# Sheet1.net
KiCad netlist of a schematic drawn in Altium Designer
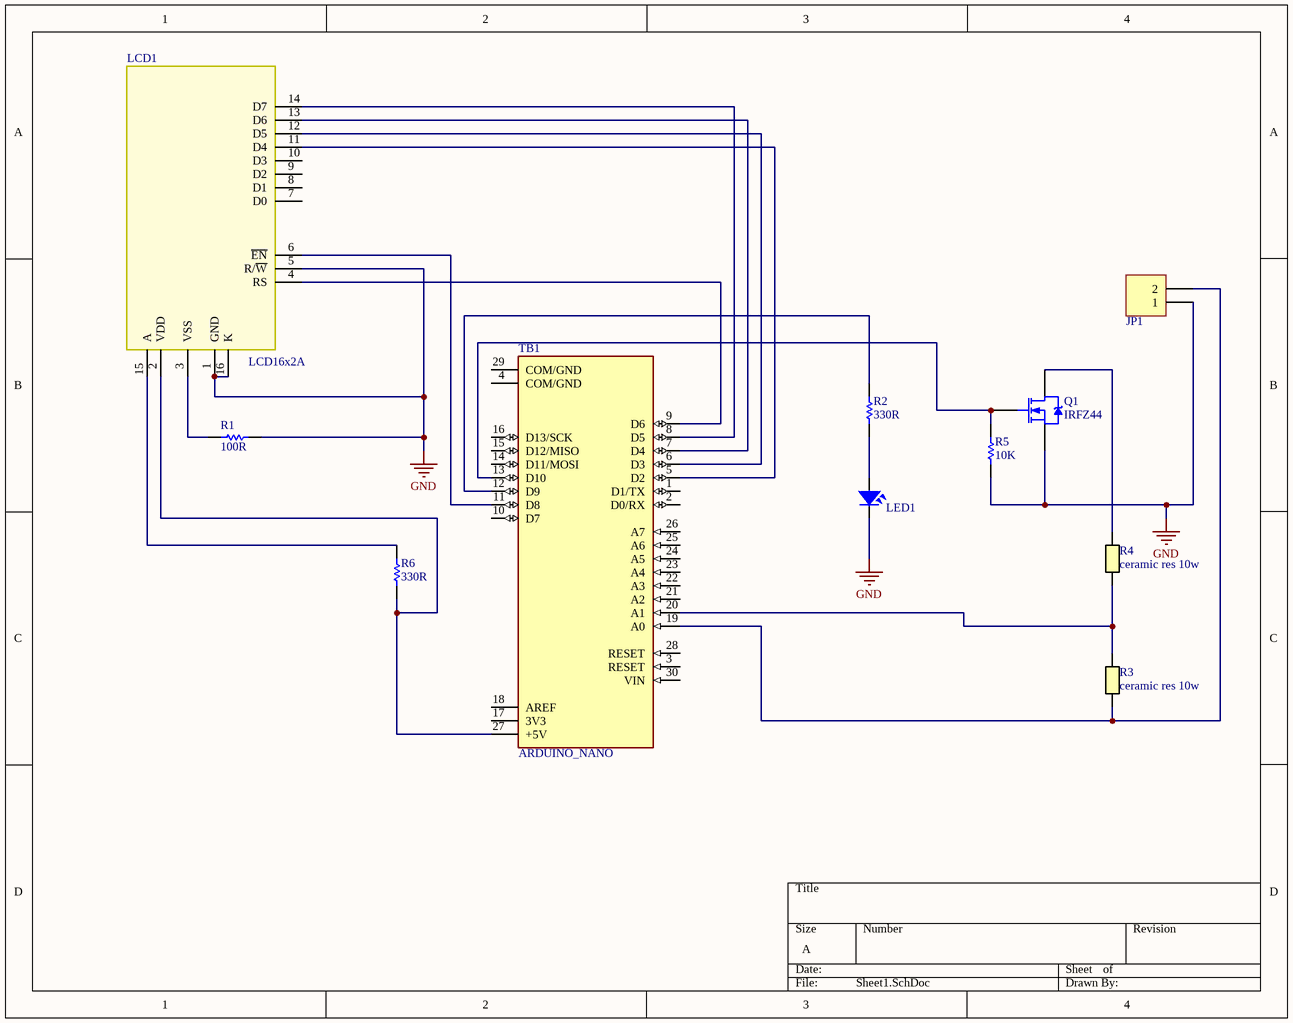
[diagram p0: Sheet1.SchDoc]

(export (version "E")
  (design (tool "Eeschema 10.0.6"))
  (components
    (comp (ref "JP1")
      (value "Header 2_1")
      (footprint "HED2")
      (description "Header, 2-Pin")
      (fields (field (name "MANUFACTURER") "Generic Components"))
      (libsource (lib "syhaunguyen") (part "Header 2_1"))
    )
    (comp (ref "LCD1")
      (value "LCD16x2A")
      (footprint "LCD16X2")
      (description "LCD dipslay 16 char, 2 line")
      (libsource (lib "syhaunguyen") (part "LCD16x2"))
    )
    (comp (ref "LED1")
      (value "LED")
      (footprint "LED-3")
      (description "LED Single colour Green and Red")
      (libsource (lib "syhaunguyen") (part "LED"))
    )
    (comp (ref "Q1")
      (value "IRFZ44")
      (footprint "QTO-220H3")
      (description "HEXFET N-Channel Power MOSFET")
      (libsource (lib "syhaunguyen") (part "IRFZ44"))
    )
    (comp (ref "R1")
      (value "100R")
      (footprint "R1/4W")
      (description "Resistor")
      (fields
        (field (name "MANUFACTURER") "Generic Components")
        (field (name "Comment") "Res1")
        (field (name "PUBLISHER") "Altium Hobart Technology Centre")
      )
      (libsource (lib "syhaunguyen") (part "Res1_1"))
    )
    (comp (ref "R2")
      (value "330R")
      (footprint "R1/4W")
      (description "Resistor")
      (fields
        (field (name "MANUFACTURER") "Generic Components")
        (field (name "Comment") "Res1")
        (field (name "PUBLISHER") "Altium Hobart Technology Centre")
      )
      (libsource (lib "syhaunguyen") (part "Res1_1"))
    )
    (comp (ref "R3")
      (value "ceramic res 10w")
      (footprint "ceramic res 10w")
      (libsource (lib "Schlib1") (part "ceramic res 10w"))
    )
    (comp (ref "R4")
      (value "ceramic res 10w")
      (footprint "ceramic res 10w")
      (libsource (lib "Schlib1") (part "ceramic res 10w"))
    )
    (comp (ref "R5")
      (value "10K")
      (footprint "R1/4W")
      (description "Resistor")
      (fields
        (field (name "MANUFACTURER") "Generic Components")
        (field (name "Comment") "Res1")
        (field (name "PUBLISHER") "Altium Hobart Technology Centre")
      )
      (libsource (lib "syhaunguyen") (part "Res1_1"))
    )
    (comp (ref "R6")
      (value "330R")
      (footprint "R1/4W")
      (description "Resistor")
      (fields
        (field (name "MANUFACTURER") "Generic Components")
        (field (name "Comment") "Res1")
        (field (name "PUBLISHER") "Altium Hobart Technology Centre")
      )
      (libsource (lib "syhaunguyen") (part "Res1_1"))
    )
    (comp (ref "TB1")
      (value "ARDUINO_NANO")
      (footprint "SHIELD_ARDUINO_NANO")
      (description "Small, complete, and breadboard-friendly board based on the ATmega328 (Arduino Nano 3.x)")
      (fields (field (name "MP") "Arduino Nano") (field (name "MF") "Arduino"))
      (libsource (lib "ARDUINO_NANO") (part "ARDUINO_NANO"))
    )
  )
  (nets
    (net (code "1") (name "GND") (class "Default")
      (node (ref "JP1") (pin "1") (pinfunction "1_1") (pintype "passive"))
      (node (ref "LCD1") (pin "1") (pinfunction "GND_1") (pintype "passive"))
      (node (ref "LCD1") (pin "16") (pinfunction "K_16") (pintype "passive"))
      (node (ref "LCD1") (pin "5") (pinfunction "R/~{W}_5") (pintype "passive"))
      (node (ref "LED1") (pin "2") (pinfunction "2_2") (pintype "passive"))
      (node (ref "Q1") (pin "3") (pinfunction "S_3") (pintype "passive"))
      (node (ref "R1") (pin "1") (pinfunction "1_1") (pintype "passive"))
      (node (ref "R5") (pin "1") (pinfunction "1_1") (pintype "passive"))
    )
    (net (code "2") (name "Net-(LCD1-A)") (class "Default")
      (node (ref "LCD1") (pin "15") (pinfunction "A_15") (pintype "passive"))
      (node (ref "R6") (pin "2") (pinfunction "2_2") (pintype "passive"))
    )
    (net (code "3") (name "Net-(LCD1-D4)") (class "Default")
      (node (ref "LCD1") (pin "11") (pinfunction "D4_11") (pintype "passive"))
      (node (ref "TB1") (pin "5") (pinfunction "D2_5") (pintype "bidirectional"))
    )
    (net (code "4") (name "Net-(LCD1-D5)") (class "Default")
      (node (ref "LCD1") (pin "12") (pinfunction "D5_12") (pintype "passive"))
      (node (ref "TB1") (pin "6") (pinfunction "D3_6") (pintype "bidirectional"))
    )
    (net (code "5") (name "Net-(LCD1-D6)") (class "Default")
      (node (ref "LCD1") (pin "13") (pinfunction "D6_13") (pintype "passive"))
      (node (ref "TB1") (pin "7") (pinfunction "D4_7") (pintype "bidirectional"))
    )
    (net (code "6") (name "Net-(LCD1-D7)") (class "Default")
      (node (ref "LCD1") (pin "14") (pinfunction "D7_14") (pintype "passive"))
      (node (ref "TB1") (pin "8") (pinfunction "D5_8") (pintype "bidirectional"))
    )
    (net (code "7") (name "Net-(LCD1-RS)") (class "Default")
      (node (ref "LCD1") (pin "4") (pinfunction "RS_4") (pintype "passive"))
      (node (ref "TB1") (pin "9") (pinfunction "D6_9") (pintype "bidirectional"))
    )
    (net (code "8") (name "Net-(LCD1-VDD)") (class "Default")
      (node (ref "LCD1") (pin "2") (pinfunction "VDD_2") (pintype "passive"))
      (node (ref "R6") (pin "1") (pinfunction "1_1") (pintype "passive"))
      (node (ref "TB1") (pin "27") (pinfunction "+5V_27") (pintype "power_in"))
    )
    (net (code "9") (name "Net-(LCD1-VSS)") (class "Default")
      (node (ref "LCD1") (pin "3") (pinfunction "VSS_3") (pintype "passive"))
      (node (ref "R1") (pin "2") (pinfunction "2_2") (pintype "passive"))
    )
    (net (code "10") (name "Net-(LCD1-~{EN})") (class "Default")
      (node (ref "LCD1") (pin "6") (pinfunction "~{EN}_6") (pintype "passive"))
      (node (ref "TB1") (pin "11") (pinfunction "D8_11") (pintype "bidirectional"))
    )
    (net (code "11") (name "Net-(LED1-Pad1)") (class "Default")
      (node (ref "LED1") (pin "1") (pinfunction "1_1") (pintype "passive"))
      (node (ref "R2") (pin "1") (pinfunction "1_1") (pintype "passive"))
    )
    (net (code "12") (name "Net-(Q1-D)") (class "Default")
      (node (ref "Q1") (pin "2") (pinfunction "D_2") (pintype "passive"))
      (node (ref "R4") (pin "2") (pinfunction "2_2") (pintype "passive"))
    )
    (net (code "13") (name "Net-(Q1-G)") (class "Default")
      (node (ref "Q1") (pin "1") (pinfunction "G_1") (pintype "passive"))
      (node (ref "R5") (pin "2") (pinfunction "2_2") (pintype "passive"))
      (node (ref "TB1") (pin "13") (pinfunction "D10_13") (pintype "bidirectional"))
    )
    (net (code "14") (name "Net-(TB1-A0)") (class "Default")
      (node (ref "JP1") (pin "2") (pinfunction "2_2") (pintype "passive"))
      (node (ref "R3") (pin "1") (pinfunction "1_1") (pintype "passive"))
      (node (ref "TB1") (pin "19") (pinfunction "A0_19") (pintype "input"))
    )
    (net (code "15") (name "Net-(TB1-A1)") (class "Default")
      (node (ref "R3") (pin "2") (pinfunction "2_2") (pintype "passive"))
      (node (ref "R4") (pin "1") (pinfunction "1_1") (pintype "passive"))
      (node (ref "TB1") (pin "20") (pinfunction "A1_20") (pintype "input"))
    )
    (net (code "16") (name "Net-(TB1-D9)") (class "Default")
      (node (ref "R2") (pin "2") (pinfunction "2_2") (pintype "passive"))
      (node (ref "TB1") (pin "12") (pinfunction "D9_12") (pintype "bidirectional"))
    )
    (net (code "17") (name "unconnected-(LCD1-D0-Pad7)") (class "Default")
      (node (ref "LCD1") (pin "7") (pinfunction "D0_7") (pintype "passive"))
    )
    (net (code "18") (name "unconnected-(LCD1-D1-Pad8)") (class "Default")
      (node (ref "LCD1") (pin "8") (pinfunction "D1_8") (pintype "passive"))
    )
    (net (code "19") (name "unconnected-(LCD1-D2-Pad9)") (class "Default")
      (node (ref "LCD1") (pin "9") (pinfunction "D2_9") (pintype "passive"))
    )
    (net (code "20") (name "unconnected-(LCD1-D3-Pad10)") (class "Default")
      (node (ref "LCD1") (pin "10") (pinfunction "D3_10") (pintype "passive"))
    )
    (net (code "21") (name "unconnected-(TB1-3V3-Pad17)") (class "Default")
      (node (ref "TB1") (pin "17") (pinfunction "3V3_17") (pintype "power_in"))
    )
    (net (code "22") (name "unconnected-(TB1-A2-Pad21)") (class "Default")
      (node (ref "TB1") (pin "21") (pinfunction "A2_21") (pintype "input"))
    )
    (net (code "23") (name "unconnected-(TB1-A3-Pad22)") (class "Default")
      (node (ref "TB1") (pin "22") (pinfunction "A3_22") (pintype "input"))
    )
    (net (code "24") (name "unconnected-(TB1-A4-Pad23)") (class "Default")
      (node (ref "TB1") (pin "23") (pinfunction "A4_23") (pintype "input"))
    )
    (net (code "25") (name "unconnected-(TB1-A5-Pad24)") (class "Default")
      (node (ref "TB1") (pin "24") (pinfunction "A5_24") (pintype "input"))
    )
    (net (code "26") (name "unconnected-(TB1-A6-Pad25)") (class "Default")
      (node (ref "TB1") (pin "25") (pinfunction "A6_25") (pintype "input"))
    )
    (net (code "27") (name "unconnected-(TB1-A7-Pad26)") (class "Default")
      (node (ref "TB1") (pin "26") (pinfunction "A7_26") (pintype "input"))
    )
    (net (code "28") (name "unconnected-(TB1-AREF-Pad18)") (class "Default")
      (node (ref "TB1") (pin "18") (pinfunction "AREF_18") (pintype "power_in"))
    )
    (net (code "29") (name "unconnected-(TB1-COM{slash}GND-Pad4)") (class "Default")
      (node (ref "TB1") (pin "4") (pinfunction "COM/GND_4") (pintype "power_in"))
    )
    (net (code "30") (name "unconnected-(TB1-COM{slash}GND-Pad29)") (class "Default")
      (node (ref "TB1") (pin "29") (pinfunction "COM/GND_29") (pintype "power_in"))
    )
    (net (code "31") (name "unconnected-(TB1-D0{slash}RX-Pad2)") (class "Default")
      (node (ref "TB1") (pin "2") (pinfunction "D0/RX_2") (pintype "bidirectional"))
    )
    (net (code "32") (name "unconnected-(TB1-D1{slash}TX-Pad1)") (class "Default")
      (node (ref "TB1") (pin "1") (pinfunction "D1/TX_1") (pintype "bidirectional"))
    )
    (net (code "33") (name "unconnected-(TB1-D7-Pad10)") (class "Default")
      (node (ref "TB1") (pin "10") (pinfunction "D7_10") (pintype "bidirectional"))
    )
    (net (code "34") (name "unconnected-(TB1-D11{slash}MOSI-Pad14)") (class "Default")
      (node (ref "TB1") (pin "14") (pinfunction "D11/MOSI_14") (pintype "bidirectional"))
    )
    (net (code "35") (name "unconnected-(TB1-D12{slash}MISO-Pad15)") (class "Default")
      (node (ref "TB1") (pin "15") (pinfunction "D12/MISO_15") (pintype "bidirectional"))
    )
    (net (code "36") (name "unconnected-(TB1-D13{slash}SCK-Pad16)") (class "Default")
      (node (ref "TB1") (pin "16") (pinfunction "D13/SCK_16") (pintype "bidirectional"))
    )
    (net (code "37") (name "unconnected-(TB1-RESET-Pad3)") (class "Default")
      (node (ref "TB1") (pin "3") (pinfunction "RESET_3") (pintype "input"))
    )
    (net (code "38") (name "unconnected-(TB1-RESET-Pad28)") (class "Default")
      (node (ref "TB1") (pin "28") (pinfunction "RESET_28") (pintype "input"))
    )
    (net (code "39") (name "unconnected-(TB1-VIN-Pad30)") (class "Default")
      (node (ref "TB1") (pin "30") (pinfunction "VIN_30") (pintype "input"))
    )
  )
)
